# Bipolar_PSU_Sheet.net
KiCad netlist of a schematic drawn in Altium Designer
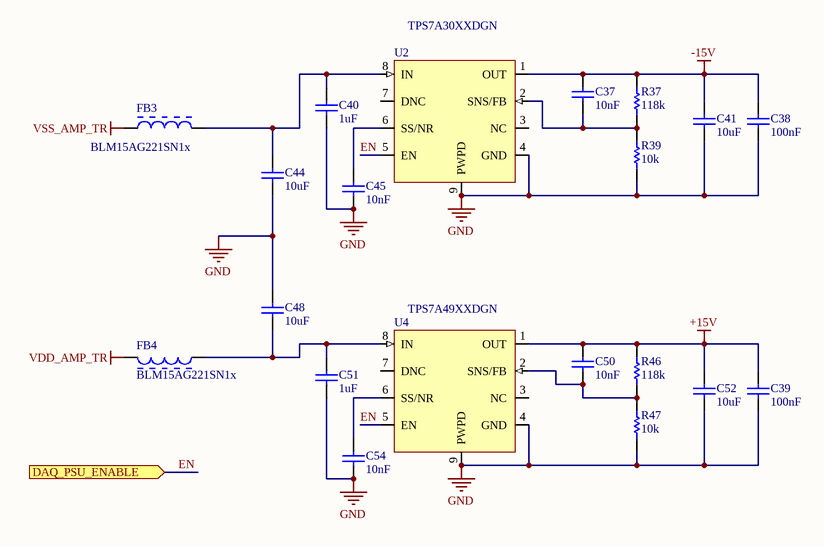
[diagram p0: Bipolar_PSU_Sheet.SchDoc]

(export (version "E")
  (design (tool "Eeschema 10.0.6"))
  (components
    (comp (ref "C37")
      (value "10nF")
      (footprint "CAPC0402(1005)60_L")
      (description "0402 (1005 Metric) Chip Capacitor")
      (fields (field (name "Comment") "CAP0402"))
      (libsource (lib "Altium Content Vault") (part "CMP-1590-00004-1"))
    )
    (comp (ref "C38")
      (value "100nF")
      (footprint "CAPC0402(1005)60_L")
      (description "0402 (1005 Metric) Chip Capacitor")
      (fields (field (name "Comment") "CAP0402"))
      (libsource (lib "Altium Content Vault") (part "CMP-1590-00004-1"))
    )
    (comp (ref "C39")
      (value "100nF")
      (footprint "CAPC0402(1005)60_L")
      (description "0402 (1005 Metric) Chip Capacitor")
      (fields (field (name "Comment") "CAP0402"))
      (libsource (lib "Altium Content Vault") (part "CMP-1590-00004-1"))
    )
    (comp (ref "C40")
      (value "1uF")
      (footprint "0603")
      (description "Capacitor")
      (fields (field (name "MANUFACTURER PART NUMBER") "0603X105K250CT"))
      (libsource (lib "Kilian_UCC_Library") (part "C_0603_1uF_25V_CER"))
    )
    (comp (ref "C41")
      (value "10uF")
      (footprint "C1206")
      (description "Capacitor")
      (fields (field (name "MANUFACTURER PART NUMBER") "1206X106K250CT"))
      (libsource (lib "Kilian_UCC_Library") (part "C_1206_10uF_25V_CER"))
    )
    (comp (ref "C44")
      (value "10uF")
      (footprint "C1206")
      (description "Capacitor")
      (fields (field (name "MANUFACTURER PART NUMBER") "1206X106K250CT"))
      (libsource (lib "Kilian_UCC_Library") (part "C_1206_10uF_25V_CER"))
    )
    (comp (ref "C45")
      (value "10nF")
      (footprint "CAPC0402(1005)60_L")
      (description "0402 (1005 Metric) Chip Capacitor")
      (fields (field (name "Comment") "CAP0402"))
      (libsource (lib "Altium Content Vault") (part "CMP-1590-00004-1"))
    )
    (comp (ref "C48")
      (value "10uF")
      (footprint "C1206")
      (description "Capacitor")
      (fields (field (name "MANUFACTURER PART NUMBER") "1206X106K250CT"))
      (libsource (lib "Kilian_UCC_Library") (part "C_1206_10uF_25V_CER"))
    )
    (comp (ref "C50")
      (value "10nF")
      (footprint "CAPC0402(1005)60_L")
      (description "0402 (1005 Metric) Chip Capacitor")
      (fields (field (name "Comment") "CAP0402"))
      (libsource (lib "Altium Content Vault") (part "CMP-1590-00004-1"))
    )
    (comp (ref "C51")
      (value "1uF")
      (footprint "0603")
      (description "Capacitor")
      (fields (field (name "MANUFACTURER PART NUMBER") "0603X105K250CT"))
      (libsource (lib "Kilian_UCC_Library") (part "C_0603_1uF_25V_CER"))
    )
    (comp (ref "C52")
      (value "10uF")
      (footprint "C1206")
      (description "Capacitor")
      (fields (field (name "MANUFACTURER PART NUMBER") "1206X106K250CT"))
      (libsource (lib "Kilian_UCC_Library") (part "C_1206_10uF_25V_CER"))
    )
    (comp (ref "C54")
      (value "10nF")
      (footprint "CAPC0402(1005)60_L")
      (description "0402 (1005 Metric) Chip Capacitor")
      (fields (field (name "Comment") "CAP0402"))
      (libsource (lib "Altium Content Vault") (part "CMP-1590-00004-1"))
    )
    (comp (ref "FB3")
      (value "BLM15AG221SN1x")
      (footprint "MURA-BLM15AG221SN1x_V")
      (description "Chip Bead, 220 Ohm, +/- 25 %, 100 MHz, 300 mA, -55 to 125 degC, 0402 (1005 Metric), RoHS")
      (fields (field (name "TOLERANCE") "25%"))
      (libsource (lib "Altium Content Vault") (part "CMP-1662-00018-3"))
    )
    (comp (ref "FB4")
      (value "BLM15AG221SN1x")
      (footprint "MURA-BLM15AG221SN1x_V")
      (description "Chip Bead, 220 Ohm, +/- 25 %, 100 MHz, 300 mA, -55 to 125 degC, 0402 (1005 Metric), RoHS")
      (fields (field (name "TOLERANCE") "25%"))
      (libsource (lib "Altium Content Vault") (part "CMP-1662-00018-3"))
    )
    (comp (ref "R37")
      (value "118k")
      (footprint "RESC0402(1005)_L")
      (description "0402 (1005 Metric) Chip Resistor")
      (fields (field (name "Comment") "RES0402"))
      (libsource (lib "Altium Content Vault") (part "CMP-1591-00004-1"))
    )
    (comp (ref "R39")
      (value "10k")
      (footprint "RESC0402(1005)_L")
      (description "0402 (1005 Metric) Chip Resistor")
      (fields (field (name "Comment") "RES0402"))
      (libsource (lib "Altium Content Vault") (part "CMP-1591-00004-1"))
    )
    (comp (ref "R46")
      (value "118k")
      (footprint "RESC0402(1005)_L")
      (description "0402 (1005 Metric) Chip Resistor")
      (fields (field (name "Comment") "RES0402"))
      (libsource (lib "Altium Content Vault") (part "CMP-1591-00004-1"))
    )
    (comp (ref "R47")
      (value "10k")
      (footprint "RESC0402(1005)_L")
      (description "0402 (1005 Metric) Chip Resistor")
      (fields (field (name "Comment") "RES0402"))
      (libsource (lib "Altium Content Vault") (part "CMP-1591-00004-1"))
    )
    (comp (ref "U2")
      (value "TPS7A30XXDGN")
      (footprint "DGN-8")
      (description "IC, -3V to -36V, -200mA, Ultralow Noise, High-PSRR LDO Negative Linear Regulator")
      (fields (field (name "MANUFACTURER") "TI") (field (name "PARTNUMBER") "TPS7A3001DGNT"))
      (libsource (lib "Kilian_UCC_Library") (part "TPS7A30XXDGN"))
    )
    (comp (ref "U4")
      (value "TPS7A49XXDGN")
      (footprint "DGN-8")
      (description "IC, 3V to 36V, 150mA, Ultralow Noise, High-PSRR LDO Positive Linear Regulator")
      (fields (field (name "MANUFACTURER") "TI") (field (name "PARTNUMBER") "TPS7A4901DGNT"))
      (libsource (lib "Kilian_UCC_Library") (part "TPS7A49XXDGN"))
    )
  )
  (nets
    (net (code "1") (name "+15V") (class "Default")
      (node (ref "C39") (pin "2") (pinfunction "2_2") (pintype "passive"))
      (node (ref "C50") (pin "2") (pinfunction "2_2") (pintype "passive"))
      (node (ref "C52") (pin "2") (pinfunction "2_2") (pintype "passive"))
      (node (ref "R46") (pin "2") (pinfunction "2_2") (pintype "passive"))
      (node (ref "U4") (pin "1") (pinfunction "OUT_1") (pintype "power_in"))
    )
    (net (code "2") (name "-15V") (class "Default")
      (node (ref "C37") (pin "2") (pinfunction "2_2") (pintype "passive"))
      (node (ref "C38") (pin "2") (pinfunction "2_2") (pintype "passive"))
      (node (ref "C41") (pin "2") (pinfunction "2_2") (pintype "passive"))
      (node (ref "R37") (pin "2") (pinfunction "2_2") (pintype "passive"))
      (node (ref "U2") (pin "1") (pinfunction "OUT_1") (pintype "power_in"))
    )
    (net (code "3") (name "/EN") (class "Default")
      (node (ref "U2") (pin "5") (pinfunction "EN_5") (pintype "passive"))
      (node (ref "U4") (pin "5") (pinfunction "EN_5") (pintype "passive"))
    )
    (net (code "4") (name "GND") (class "Default")
      (node (ref "C38") (pin "1") (pinfunction "1_1") (pintype "passive"))
      (node (ref "C39") (pin "1") (pinfunction "1_1") (pintype "passive"))
      (node (ref "C40") (pin "1") (pinfunction "1_1") (pintype "passive"))
      (node (ref "C41") (pin "1") (pinfunction "1_1") (pintype "passive"))
      (node (ref "C44") (pin "1") (pinfunction "1_1") (pintype "passive"))
      (node (ref "C45") (pin "1") (pinfunction "1_1") (pintype "passive"))
      (node (ref "C48") (pin "2") (pinfunction "2_2") (pintype "passive"))
      (node (ref "C51") (pin "1") (pinfunction "1_1") (pintype "passive"))
      (node (ref "C52") (pin "1") (pinfunction "1_1") (pintype "passive"))
      (node (ref "C54") (pin "1") (pinfunction "1_1") (pintype "passive"))
      (node (ref "R39") (pin "1") (pinfunction "1_1") (pintype "passive"))
      (node (ref "R47") (pin "1") (pinfunction "1_1") (pintype "passive"))
      (node (ref "U2") (pin "4") (pinfunction "GND_4") (pintype "power_in"))
      (node (ref "U2") (pin "9") (pinfunction "PWPD_9") (pintype "passive"))
      (node (ref "U4") (pin "4") (pinfunction "GND_4") (pintype "power_in"))
      (node (ref "U4") (pin "9") (pinfunction "PWPD_9") (pintype "passive"))
    )
    (net (code "5") (name "Net-(U2-IN)") (class "Default")
      (node (ref "C40") (pin "2") (pinfunction "2_2") (pintype "passive"))
      (node (ref "C44") (pin "2") (pinfunction "2_2") (pintype "passive"))
      (node (ref "FB3") (pin "2") (pinfunction "2_2") (pintype "passive"))
      (node (ref "U2") (pin "8") (pinfunction "IN_8") (pintype "input"))
    )
    (net (code "6") (name "Net-(U2-SNS{slash}FB)") (class "Default")
      (node (ref "C37") (pin "1") (pinfunction "1_1") (pintype "passive"))
      (node (ref "R37") (pin "1") (pinfunction "1_1") (pintype "passive"))
      (node (ref "R39") (pin "2") (pinfunction "2_2") (pintype "passive"))
      (node (ref "U2") (pin "2") (pinfunction "SNS/FB_2") (pintype "input"))
    )
    (net (code "7") (name "Net-(U2-SS{slash}NR)") (class "Default")
      (node (ref "C45") (pin "2") (pinfunction "2_2") (pintype "passive"))
      (node (ref "U2") (pin "6") (pinfunction "SS/NR_6") (pintype "passive"))
    )
    (net (code "8") (name "Net-(U4-IN)") (class "Default")
      (node (ref "C48") (pin "1") (pinfunction "1_1") (pintype "passive"))
      (node (ref "C51") (pin "2") (pinfunction "2_2") (pintype "passive"))
      (node (ref "FB4") (pin "1") (pinfunction "1_1") (pintype "passive"))
      (node (ref "U4") (pin "8") (pinfunction "IN_8") (pintype "input"))
    )
    (net (code "9") (name "Net-(U4-SNS{slash}FB)") (class "Default")
      (node (ref "C50") (pin "1") (pinfunction "1_1") (pintype "passive"))
      (node (ref "R46") (pin "1") (pinfunction "1_1") (pintype "passive"))
      (node (ref "R47") (pin "2") (pinfunction "2_2") (pintype "passive"))
      (node (ref "U4") (pin "2") (pinfunction "SNS/FB_2") (pintype "input"))
    )
    (net (code "10") (name "Net-(U4-SS{slash}NR)") (class "Default")
      (node (ref "C54") (pin "2") (pinfunction "2_2") (pintype "passive"))
      (node (ref "U4") (pin "6") (pinfunction "SS/NR_6") (pintype "passive"))
    )
    (net (code "11") (name "VDD_AMP_TR") (class "Default")
      (node (ref "FB4") (pin "2") (pinfunction "2_2") (pintype "passive"))
    )
    (net (code "12") (name "VSS_AMP_TR") (class "Default")
      (node (ref "FB3") (pin "1") (pinfunction "1_1") (pintype "passive"))
    )
    (net (code "13") (name "unconnected-(U2-DNC-Pad7)") (class "Default")
      (node (ref "U2") (pin "7") (pinfunction "DNC_7") (pintype "passive"))
    )
    (net (code "14") (name "unconnected-(U2-NC-Pad3)") (class "Default")
      (node (ref "U2") (pin "3") (pinfunction "NC_3") (pintype "passive"))
    )
    (net (code "15") (name "unconnected-(U4-DNC-Pad7)") (class "Default")
      (node (ref "U4") (pin "7") (pinfunction "DNC_7") (pintype "passive"))
    )
    (net (code "16") (name "unconnected-(U4-NC-Pad3)") (class "Default")
      (node (ref "U4") (pin "3") (pinfunction "NC_3") (pintype "passive"))
    )
  )
)
